# 5V_to_3V3_LDO.net
KiCad netlist of a schematic drawn in Altium Designer
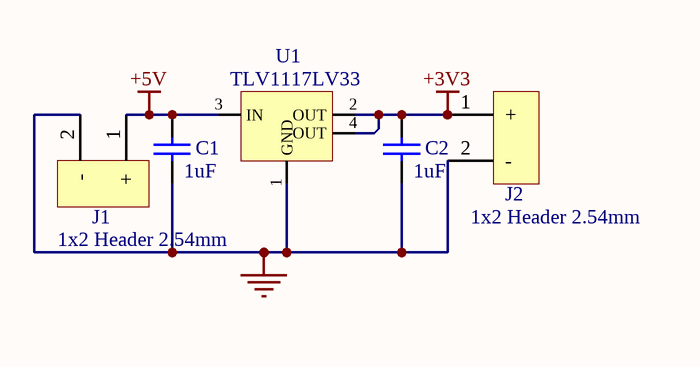
[diagram p0: 5V_to_3V3_LDO.SchDoc]

(export (version "E")
  (design (tool "Eeschema 10.0.6"))
  (components
    (comp (ref "C1")
      (value "1uF")
      (footprint "C0805")
      (description "Ceramic Capacitor, 0805 (2012 Metric)")
      (fields (field (name "PUBLISHER") "Altium Limited"))
      (libsource (lib "5V_to_3V3_LDO") (part "CAP_C0805"))
    )
    (comp (ref "C2")
      (value "1uF")
      (footprint "C0805")
      (description "Ceramic Capacitor, 0805 (2012 Metric)")
      (fields (field (name "PUBLISHER") "Altium Limited"))
      (libsource (lib "5V_to_3V3_LDO") (part "CAP_C0805"))
    )
    (comp (ref "J1")
      (value "1x2 Header 2.54mm")
      (footprint "PINHDR_1x02_P2.54_VERT")
      (description "2-pin vertical male header, 2.54mm pitch, through-hole")
      (fields
        (field (name "MANUFACTURER") "Wurth Elektronik")
        (field (name "MANUFACTURER PART NUMBER") "61300211121")
      )
      (libsource (lib "5V_to_3V3_LDO") (part "61300211121"))
    )
    (comp (ref "J2")
      (value "1x2 Header 2.54mm")
      (footprint "PINHDR_1x02_P2.54_VERT")
      (description "2-pin vertical male header, 2.54mm pitch, through-hole")
      (fields
        (field (name "MANUFACTURER") "Wurth Elektronik")
        (field (name "MANUFACTURER PART NUMBER") "61300211121")
      )
      (libsource (lib "") (part "61300211121_1"))
    )
    (comp (ref "U1")
      (value "TLV1117LV33")
      (footprint "5V_to_3V3_LDO:TLV1117LV33DCYT")
      (description "1-A, 3.3-V Fixed-Output LDO Regulator")
      (libsource (lib "5V_to_3V3_LDO") (part "TLV1117LV33"))
    )
  )
  (nets
    (net (code "1") (name "+3V3") (class "Default")
      (node (ref "C2") (pin "2") (pinfunction "2_2") (pintype "passive"))
      (node (ref "J2") (pin "1") (pinfunction "+_1") (pintype "passive"))
      (node (ref "U1") (pin "2") (pinfunction "OUT_2") (pintype "power_in"))
      (node (ref "U1") (pin "4") (pinfunction "OUT_4") (pintype "power_in"))
    )
    (net (code "2") (name "+5V") (class "Default")
      (node (ref "C1") (pin "2") (pinfunction "2_2") (pintype "passive"))
      (node (ref "J1") (pin "1") (pinfunction "+_1") (pintype "passive"))
      (node (ref "U1") (pin "3") (pinfunction "IN_3") (pintype "power_in"))
    )
    (net (code "3") (name "GND") (class "Default")
      (node (ref "C1") (pin "1") (pinfunction "1_1") (pintype "passive"))
      (node (ref "C2") (pin "1") (pinfunction "1_1") (pintype "passive"))
      (node (ref "J1") (pin "2") (pinfunction "-_2") (pintype "passive"))
      (node (ref "J2") (pin "2") (pinfunction "-_2") (pintype "passive"))
      (node (ref "U1") (pin "1") (pinfunction "GND_1") (pintype "power_in"))
    )
  )
)
